# Turnout_Decoder_V1_2.net
KiCad netlist of a schematic drawn in EAGLE
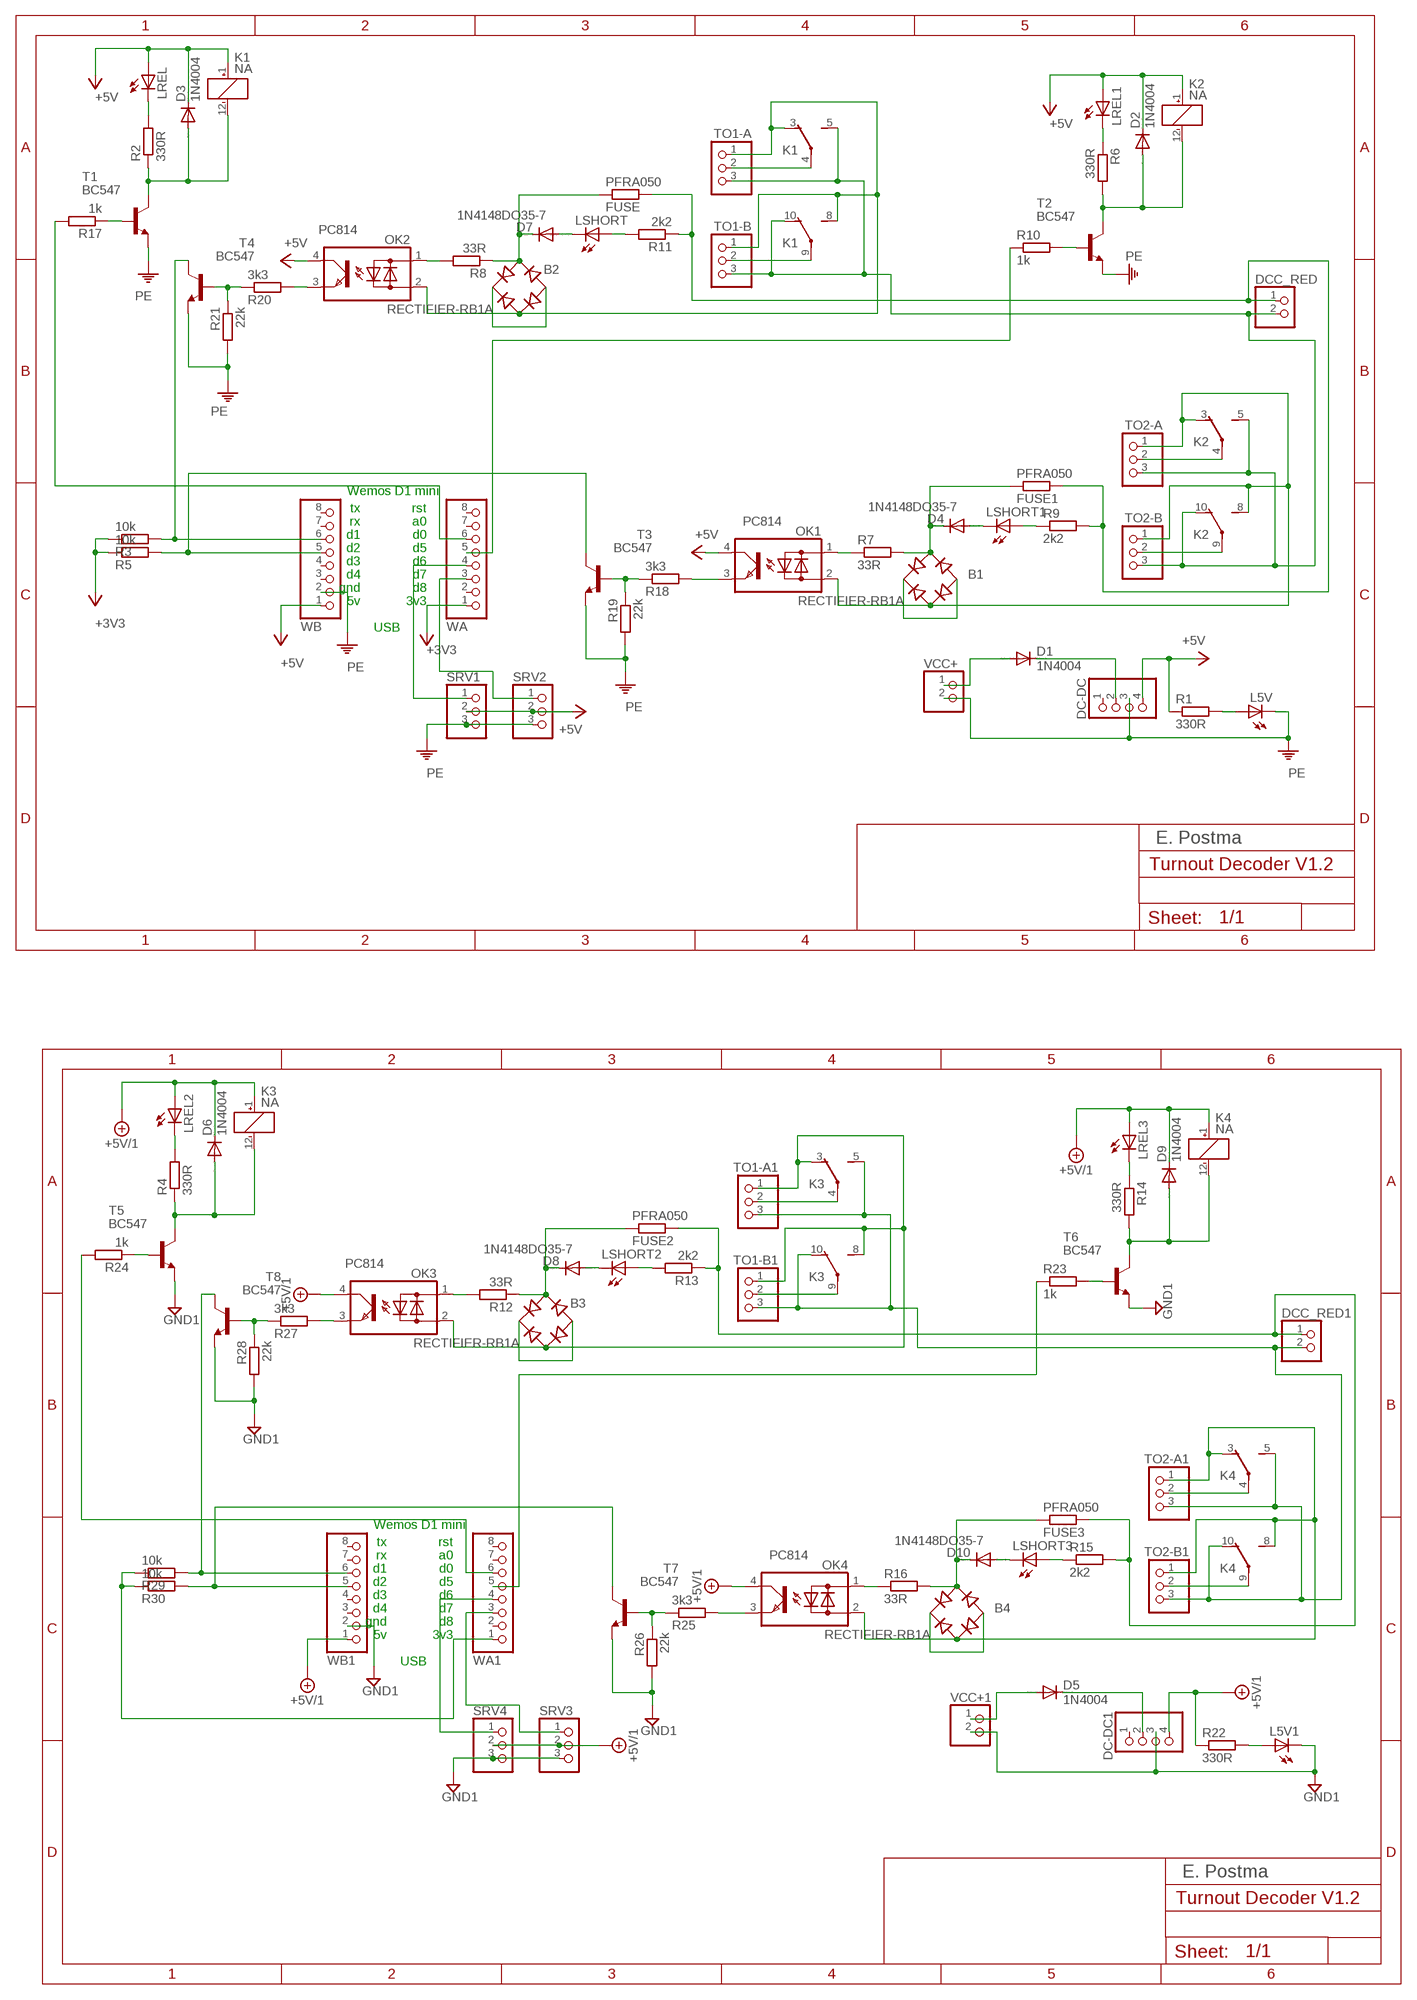
[diagram p0: schematic, sheet 1]

(export (version "E")
  (design (tool "Eeschema 10.0.6"))
  (components
    (comp (ref "B1")
      (value "RECTIFIER-RB1A")
      (footprint "eagle-import:RB1A")
      (libsource (lib "eagle-import") (part "RECTIFIER-RB1A"))
    )
    (comp (ref "B2")
      (value "RECTIFIER-RB1A")
      (footprint "eagle-import:RB1A")
      (libsource (lib "eagle-import") (part "RECTIFIER-RB1A"))
    )
    (comp (ref "B3")
      (value "RECTIFIER-RB1A")
      (footprint "eagle-import:RB1A")
      (libsource (lib "eagle-import") (part "RECTIFIER-RB1A"))
    )
    (comp (ref "B4")
      (value "RECTIFIER-RB1A")
      (footprint "eagle-import:RB1A")
      (libsource (lib "eagle-import") (part "RECTIFIER-RB1A"))
    )
    (comp (ref "D1")
      (value "1N4004")
      (footprint "eagle-import:DO41-10")
      (libsource (lib "eagle-import") (part "1N4004"))
    )
    (comp (ref "D2")
      (value "1N4004")
      (footprint "eagle-import:DO41-10")
      (libsource (lib "eagle-import") (part "1N4004"))
    )
    (comp (ref "D3")
      (value "1N4004")
      (footprint "eagle-import:DO41-10")
      (libsource (lib "eagle-import") (part "1N4004"))
    )
    (comp (ref "D4")
      (value "1N4148DO35-7")
      (footprint "eagle-import:DO35-7")
      (libsource (lib "eagle-import") (part "1N4148DO35-7"))
    )
    (comp (ref "D5")
      (value "1N4004")
      (footprint "eagle-import:DO41-10")
      (libsource (lib "eagle-import") (part "1N4004"))
    )
    (comp (ref "D6")
      (value "1N4004")
      (footprint "eagle-import:DO41-10")
      (libsource (lib "eagle-import") (part "1N4004"))
    )
    (comp (ref "D7")
      (value "1N4148DO35-7")
      (footprint "eagle-import:DO35-7")
      (libsource (lib "eagle-import") (part "1N4148DO35-7"))
    )
    (comp (ref "D8")
      (value "1N4148DO35-7")
      (footprint "eagle-import:DO35-7")
      (libsource (lib "eagle-import") (part "1N4148DO35-7"))
    )
    (comp (ref "D9")
      (value "1N4004")
      (footprint "eagle-import:DO41-10")
      (libsource (lib "eagle-import") (part "1N4004"))
    )
    (comp (ref "D10")
      (value "1N4148DO35-7")
      (footprint "eagle-import:DO35-7")
      (libsource (lib "eagle-import") (part "1N4148DO35-7"))
    )
    (comp (ref "DC-DC")
      (value "PINHD-1X4")
      (footprint "eagle-import:1X04")
      (libsource (lib "eagle-import") (part "PINHD-1X4"))
    )
    (comp (ref "DC-DC1")
      (value "PINHD-1X4")
      (footprint "eagle-import:1X04")
      (libsource (lib "eagle-import") (part "PINHD-1X4"))
    )
    (comp (ref "DCC_RED")
      (value "PINHD-1X2")
      (footprint "eagle-import:1X02")
      (libsource (lib "eagle-import") (part "PINHD-1X2"))
    )
    (comp (ref "DCC_RED1")
      (value "PINHD-1X2")
      (footprint "eagle-import:1X02")
      (libsource (lib "eagle-import") (part "PINHD-1X2"))
    )
    (comp (ref "FUSE")
      (value "PFRA050")
      (footprint "eagle-import:0414V")
      (libsource (lib "eagle-import") (part "R-EU_0414/5V"))
    )
    (comp (ref "FUSE1")
      (value "PFRA050")
      (footprint "eagle-import:0414V")
      (libsource (lib "eagle-import") (part "R-EU_0414/5V"))
    )
    (comp (ref "FUSE2")
      (value "PFRA050")
      (footprint "eagle-import:0414V")
      (libsource (lib "eagle-import") (part "R-EU_0414/5V"))
    )
    (comp (ref "FUSE3")
      (value "PFRA050")
      (footprint "eagle-import:0414V")
      (libsource (lib "eagle-import") (part "R-EU_0414/5V"))
    )
    (comp (ref "K1") (value "NA") (footprint "eagle-import:NA") (libsource (lib "eagle-import") (part "NA")))
    (comp (ref "K2") (value "NA") (footprint "eagle-import:NA") (libsource (lib "eagle-import") (part "NA")))
    (comp (ref "K3") (value "NA") (footprint "eagle-import:NA") (libsource (lib "eagle-import") (part "NA")))
    (comp (ref "K4") (value "NA") (footprint "eagle-import:NA") (libsource (lib "eagle-import") (part "NA")))
    (comp (ref "L5V")
      (value "LED3MM")
      (footprint "eagle-import:LED3MM")
      (libsource (lib "eagle-import") (part "LED3MM"))
    )
    (comp (ref "L5V1")
      (value "LED3MM")
      (footprint "eagle-import:LED3MM")
      (libsource (lib "eagle-import") (part "LED3MM"))
    )
    (comp (ref "LREL")
      (value "LED3MM")
      (footprint "eagle-import:LED3MM")
      (libsource (lib "eagle-import") (part "LED3MM"))
    )
    (comp (ref "LREL1")
      (value "LED3MM")
      (footprint "eagle-import:LED3MM")
      (libsource (lib "eagle-import") (part "LED3MM"))
    )
    (comp (ref "LREL2")
      (value "LED3MM")
      (footprint "eagle-import:LED3MM")
      (libsource (lib "eagle-import") (part "LED3MM"))
    )
    (comp (ref "LREL3")
      (value "LED3MM")
      (footprint "eagle-import:LED3MM")
      (libsource (lib "eagle-import") (part "LED3MM"))
    )
    (comp (ref "LSHORT")
      (value "LED3MM")
      (footprint "eagle-import:LED3MM")
      (libsource (lib "eagle-import") (part "LED3MM"))
    )
    (comp (ref "LSHORT1")
      (value "LED3MM")
      (footprint "eagle-import:LED3MM")
      (libsource (lib "eagle-import") (part "LED3MM"))
    )
    (comp (ref "LSHORT2")
      (value "LED3MM")
      (footprint "eagle-import:LED3MM")
      (libsource (lib "eagle-import") (part "LED3MM"))
    )
    (comp (ref "LSHORT3")
      (value "LED3MM")
      (footprint "eagle-import:LED3MM")
      (libsource (lib "eagle-import") (part "LED3MM"))
    )
    (comp (ref "OK1")
      (value "PC814")
      (footprint "eagle-import:DIL04")
      (libsource (lib "eagle-import") (part "PC814"))
    )
    (comp (ref "OK2")
      (value "PC814")
      (footprint "eagle-import:DIL04")
      (libsource (lib "eagle-import") (part "PC814"))
    )
    (comp (ref "OK3")
      (value "PC814")
      (footprint "eagle-import:DIL04")
      (libsource (lib "eagle-import") (part "PC814"))
    )
    (comp (ref "OK4")
      (value "PC814")
      (footprint "eagle-import:DIL04")
      (libsource (lib "eagle-import") (part "PC814"))
    )
    (comp (ref "R1")
      (value "330R")
      (footprint "eagle-import:0207_7")
      (libsource (lib "eagle-import") (part "resistor_348_R-EU_0207/7"))
    )
    (comp (ref "R2")
      (value "330R")
      (footprint "eagle-import:0207_7")
      (libsource (lib "eagle-import") (part "resistor_348_R-EU_0207/7"))
    )
    (comp (ref "R3")
      (value "10k")
      (footprint "eagle-import:0207_7")
      (libsource (lib "eagle-import") (part "resistor_348_R-EU_0207/7"))
    )
    (comp (ref "R4")
      (value "330R")
      (footprint "eagle-import:0207_7")
      (libsource (lib "eagle-import") (part "resistor_348_R-EU_0207/7"))
    )
    (comp (ref "R5")
      (value "10k")
      (footprint "eagle-import:0207_7")
      (libsource (lib "eagle-import") (part "resistor_348_R-EU_0207/7"))
    )
    (comp (ref "R6")
      (value "330R")
      (footprint "eagle-import:0207_7")
      (libsource (lib "eagle-import") (part "resistor_348_R-EU_0207/7"))
    )
    (comp (ref "R7")
      (value "33R")
      (footprint "eagle-import:0207_7")
      (libsource (lib "eagle-import") (part "resistor_348_R-EU_0207/7"))
    )
    (comp (ref "R8")
      (value "33R")
      (footprint "eagle-import:0207_7")
      (libsource (lib "eagle-import") (part "resistor_348_R-EU_0207/7"))
    )
    (comp (ref "R9")
      (value "2k2")
      (footprint "eagle-import:0207_7")
      (libsource (lib "eagle-import") (part "resistor_348_R-EU_0207/7"))
    )
    (comp (ref "R10")
      (value "1k")
      (footprint "eagle-import:0207_7")
      (libsource (lib "eagle-import") (part "resistor_348_R-EU_0207/7"))
    )
    (comp (ref "R11")
      (value "2k2")
      (footprint "eagle-import:0207_7")
      (libsource (lib "eagle-import") (part "resistor_348_R-EU_0207/7"))
    )
    (comp (ref "R12")
      (value "33R")
      (footprint "eagle-import:0207_7")
      (libsource (lib "eagle-import") (part "resistor_348_R-EU_0207/7"))
    )
    (comp (ref "R13")
      (value "2k2")
      (footprint "eagle-import:0207_7")
      (libsource (lib "eagle-import") (part "resistor_348_R-EU_0207/7"))
    )
    (comp (ref "R14")
      (value "330R")
      (footprint "eagle-import:0207_7")
      (libsource (lib "eagle-import") (part "resistor_348_R-EU_0207/7"))
    )
    (comp (ref "R15")
      (value "2k2")
      (footprint "eagle-import:0207_7")
      (libsource (lib "eagle-import") (part "resistor_348_R-EU_0207/7"))
    )
    (comp (ref "R16")
      (value "33R")
      (footprint "eagle-import:0207_7")
      (libsource (lib "eagle-import") (part "resistor_348_R-EU_0207/7"))
    )
    (comp (ref "R17")
      (value "1k")
      (footprint "eagle-import:0207_7")
      (libsource (lib "eagle-import") (part "resistor_348_R-EU_0207/7"))
    )
    (comp (ref "R18")
      (value "3k3")
      (footprint "eagle-import:0207_7")
      (libsource (lib "eagle-import") (part "resistor_348_R-EU_0207/7"))
    )
    (comp (ref "R19")
      (value "22k")
      (footprint "eagle-import:0207_7")
      (libsource (lib "eagle-import") (part "resistor_348_R-EU_0207/7"))
    )
    (comp (ref "R20")
      (value "3k3")
      (footprint "eagle-import:0207_7")
      (libsource (lib "eagle-import") (part "resistor_348_R-EU_0207/7"))
    )
    (comp (ref "R21")
      (value "22k")
      (footprint "eagle-import:0207_7")
      (libsource (lib "eagle-import") (part "resistor_348_R-EU_0207/7"))
    )
    (comp (ref "R22")
      (value "330R")
      (footprint "eagle-import:0207_7")
      (libsource (lib "eagle-import") (part "resistor_348_R-EU_0207/7"))
    )
    (comp (ref "R23")
      (value "1k")
      (footprint "eagle-import:0207_7")
      (libsource (lib "eagle-import") (part "resistor_348_R-EU_0207/7"))
    )
    (comp (ref "R24")
      (value "1k")
      (footprint "eagle-import:0207_7")
      (libsource (lib "eagle-import") (part "resistor_348_R-EU_0207/7"))
    )
    (comp (ref "R25")
      (value "3k3")
      (footprint "eagle-import:0207_7")
      (libsource (lib "eagle-import") (part "resistor_348_R-EU_0207/7"))
    )
    (comp (ref "R26")
      (value "22k")
      (footprint "eagle-import:0207_7")
      (libsource (lib "eagle-import") (part "resistor_348_R-EU_0207/7"))
    )
    (comp (ref "R27")
      (value "3k3")
      (footprint "eagle-import:0207_7")
      (libsource (lib "eagle-import") (part "resistor_348_R-EU_0207/7"))
    )
    (comp (ref "R28")
      (value "22k")
      (footprint "eagle-import:0207_7")
      (libsource (lib "eagle-import") (part "resistor_348_R-EU_0207/7"))
    )
    (comp (ref "R29")
      (value "10k")
      (footprint "eagle-import:0207_7")
      (libsource (lib "eagle-import") (part "resistor_348_R-EU_0207/7"))
    )
    (comp (ref "R30")
      (value "10k")
      (footprint "eagle-import:0207_7")
      (libsource (lib "eagle-import") (part "resistor_348_R-EU_0207/7"))
    )
    (comp (ref "SRV1")
      (value "PINHD-1X3")
      (footprint "eagle-import:1X03")
      (libsource (lib "eagle-import") (part "PINHD-1X3"))
    )
    (comp (ref "SRV2")
      (value "PINHD-1X3")
      (footprint "eagle-import:1X03")
      (libsource (lib "eagle-import") (part "PINHD-1X3"))
    )
    (comp (ref "SRV3")
      (value "PINHD-1X3")
      (footprint "eagle-import:1X03")
      (libsource (lib "eagle-import") (part "PINHD-1X3"))
    )
    (comp (ref "SRV4")
      (value "PINHD-1X3")
      (footprint "eagle-import:1X03")
      (libsource (lib "eagle-import") (part "PINHD-1X3"))
    )
    (comp (ref "T1")
      (value "BC547")
      (footprint "eagle-import:TO92")
      (libsource (lib "eagle-import") (part "BC547"))
    )
    (comp (ref "T2")
      (value "BC547")
      (footprint "eagle-import:TO92")
      (libsource (lib "eagle-import") (part "BC547"))
    )
    (comp (ref "T3")
      (value "BC547")
      (footprint "eagle-import:TO92")
      (libsource (lib "eagle-import") (part "BC547"))
    )
    (comp (ref "T4")
      (value "BC547")
      (footprint "eagle-import:TO92")
      (libsource (lib "eagle-import") (part "BC547"))
    )
    (comp (ref "T5")
      (value "BC547")
      (footprint "eagle-import:TO92")
      (libsource (lib "eagle-import") (part "BC547"))
    )
    (comp (ref "T6")
      (value "BC547")
      (footprint "eagle-import:TO92")
      (libsource (lib "eagle-import") (part "BC547"))
    )
    (comp (ref "T7")
      (value "BC547")
      (footprint "eagle-import:TO92")
      (libsource (lib "eagle-import") (part "BC547"))
    )
    (comp (ref "T8")
      (value "BC547")
      (footprint "eagle-import:TO92")
      (libsource (lib "eagle-import") (part "BC547"))
    )
    (comp (ref "TO1-A")
      (value "PINHD-1X3")
      (footprint "eagle-import:1X03")
      (libsource (lib "eagle-import") (part "PINHD-1X3"))
    )
    (comp (ref "TO1-A1")
      (value "PINHD-1X3")
      (footprint "eagle-import:1X03")
      (libsource (lib "eagle-import") (part "PINHD-1X3"))
    )
    (comp (ref "TO1-B")
      (value "PINHD-1X3")
      (footprint "eagle-import:1X03")
      (libsource (lib "eagle-import") (part "PINHD-1X3"))
    )
    (comp (ref "TO1-B1")
      (value "PINHD-1X3")
      (footprint "eagle-import:1X03")
      (libsource (lib "eagle-import") (part "PINHD-1X3"))
    )
    (comp (ref "TO2-A")
      (value "PINHD-1X3")
      (footprint "eagle-import:1X03")
      (libsource (lib "eagle-import") (part "PINHD-1X3"))
    )
    (comp (ref "TO2-A1")
      (value "PINHD-1X3")
      (footprint "eagle-import:1X03")
      (libsource (lib "eagle-import") (part "PINHD-1X3"))
    )
    (comp (ref "TO2-B")
      (value "PINHD-1X3")
      (footprint "eagle-import:1X03")
      (libsource (lib "eagle-import") (part "PINHD-1X3"))
    )
    (comp (ref "TO2-B1")
      (value "PINHD-1X3")
      (footprint "eagle-import:1X03")
      (libsource (lib "eagle-import") (part "PINHD-1X3"))
    )
    (comp (ref "VCC+")
      (value "PINHD-1X2")
      (footprint "eagle-import:1X02")
      (libsource (lib "eagle-import") (part "PINHD-1X2"))
    )
    (comp (ref "VCC+1")
      (value "PINHD-1X2")
      (footprint "eagle-import:1X02")
      (libsource (lib "eagle-import") (part "PINHD-1X2"))
    )
    (comp (ref "WA")
      (value "PINHD-1X8")
      (footprint "eagle-import:1X08")
      (libsource (lib "eagle-import") (part "PINHD-1X8"))
    )
    (comp (ref "WA1")
      (value "PINHD-1X8")
      (footprint "eagle-import:1X08")
      (libsource (lib "eagle-import") (part "PINHD-1X8"))
    )
    (comp (ref "WB")
      (value "PINHD-1X8")
      (footprint "eagle-import:1X08")
      (libsource (lib "eagle-import") (part "PINHD-1X8"))
    )
    (comp (ref "WB1")
      (value "PINHD-1X8")
      (footprint "eagle-import:1X08")
      (libsource (lib "eagle-import") (part "PINHD-1X8"))
    )
  )
  (nets
    (net (code "1") (name "+3V3") (class "Default")
      (node (ref "R3") (pin "1") (pinfunction "1_1") (pintype "passive"))
      (node (ref "R5") (pin "1") (pinfunction "1_1") (pintype "passive"))
      (node (ref "WA") (pin "1") (pinfunction "1_1") (pintype "passive"))
    )
    (net (code "2") (name "+5V") (class "Default")
      (node (ref "D2") (pin "C") (pinfunction "C_C") (pintype "passive"))
      (node (ref "D3") (pin "C") (pinfunction "C_C") (pintype "passive"))
      (node (ref "DC-DC") (pin "4") (pinfunction "4_4") (pintype "passive"))
      (node (ref "K1") (pin "1") (pinfunction "+_1") (pintype "passive"))
      (node (ref "K2") (pin "1") (pinfunction "+_1") (pintype "passive"))
      (node (ref "LREL") (pin "A") (pinfunction "A_A") (pintype "passive"))
      (node (ref "LREL1") (pin "A") (pinfunction "A_A") (pintype "passive"))
      (node (ref "OK1") (pin "4") (pinfunction "C_4") (pintype "passive"))
      (node (ref "OK2") (pin "4") (pinfunction "C_4") (pintype "passive"))
      (node (ref "R1") (pin "1") (pinfunction "1_1") (pintype "passive"))
      (node (ref "SRV1") (pin "2") (pinfunction "2_2") (pintype "passive"))
      (node (ref "SRV2") (pin "2") (pinfunction "2_2") (pintype "passive"))
      (node (ref "WB") (pin "1") (pinfunction "1_1") (pintype "passive"))
    )
    (net (code "3") (name "+5V{slash}1") (class "Default")
      (node (ref "D6") (pin "C") (pinfunction "C_C") (pintype "passive"))
      (node (ref "D9") (pin "C") (pinfunction "C_C") (pintype "passive"))
      (node (ref "DC-DC1") (pin "4") (pinfunction "4_4") (pintype "passive"))
      (node (ref "K3") (pin "1") (pinfunction "+_1") (pintype "passive"))
      (node (ref "K4") (pin "1") (pinfunction "+_1") (pintype "passive"))
      (node (ref "LREL2") (pin "A") (pinfunction "A_A") (pintype "passive"))
      (node (ref "LREL3") (pin "A") (pinfunction "A_A") (pintype "passive"))
      (node (ref "OK3") (pin "4") (pinfunction "C_4") (pintype "passive"))
      (node (ref "OK4") (pin "4") (pinfunction "C_4") (pintype "passive"))
      (node (ref "R22") (pin "1") (pinfunction "1_1") (pintype "passive"))
      (node (ref "SRV3") (pin "2") (pinfunction "2_2") (pintype "passive"))
      (node (ref "SRV4") (pin "2") (pinfunction "2_2") (pintype "passive"))
      (node (ref "WB1") (pin "1") (pinfunction "1_1") (pintype "passive"))
    )
    (net (code "4") (name "GND1") (class "Default")
      (node (ref "DC-DC1") (pin "3") (pinfunction "3_3") (pintype "passive"))
      (node (ref "L5V1") (pin "K") (pinfunction "C_K") (pintype "passive"))
      (node (ref "R26") (pin "2") (pinfunction "2_2") (pintype "passive"))
      (node (ref "R28") (pin "2") (pinfunction "2_2") (pintype "passive"))
      (node (ref "SRV3") (pin "3") (pinfunction "3_3") (pintype "passive"))
      (node (ref "SRV4") (pin "3") (pinfunction "3_3") (pintype "passive"))
      (node (ref "T5") (pin "1") (pinfunction "E_1") (pintype "passive"))
      (node (ref "T6") (pin "1") (pinfunction "E_1") (pintype "passive"))
      (node (ref "T7") (pin "1") (pinfunction "E_1") (pintype "passive"))
      (node (ref "T8") (pin "1") (pinfunction "E_1") (pintype "passive"))
      (node (ref "VCC+1") (pin "2") (pinfunction "2_2") (pintype "passive"))
      (node (ref "WB1") (pin "2") (pinfunction "2_2") (pintype "passive"))
    )
    (net (code "5") (name "Net-(B1-Pad+)") (class "Default")
      (node (ref "B1") (pin "+") (pinfunction "+_+") (pintype "passive"))
      (node (ref "B1") (pin "-") (pinfunction "-_-") (pintype "passive"))
    )
    (net (code "6") (name "Net-(B1-PadAC1)") (class "Default")
      (node (ref "B1") (pin "AC1") (pinfunction "AC1_AC1") (pintype "passive"))
      (node (ref "D4") (pin "C") (pinfunction "C_C") (pintype "passive"))
      (node (ref "FUSE1") (pin "1") (pinfunction "1_1") (pintype "passive"))
      (node (ref "R7") (pin "2") (pinfunction "2_2") (pintype "passive"))
    )
    (net (code "7") (name "Net-(B2-Pad+)") (class "Default")
      (node (ref "B2") (pin "+") (pinfunction "+_+") (pintype "passive"))
      (node (ref "B2") (pin "-") (pinfunction "-_-") (pintype "passive"))
    )
    (net (code "8") (name "Net-(B2-PadAC1)") (class "Default")
      (node (ref "B2") (pin "AC1") (pinfunction "AC1_AC1") (pintype "passive"))
      (node (ref "D7") (pin "C") (pinfunction "C_C") (pintype "passive"))
      (node (ref "FUSE") (pin "1") (pinfunction "1_1") (pintype "passive"))
      (node (ref "R8") (pin "1") (pinfunction "1_1") (pintype "passive"))
    )
    (net (code "9") (name "Net-(B3-Pad+)") (class "Default")
      (node (ref "B3") (pin "+") (pinfunction "+_+") (pintype "passive"))
      (node (ref "B3") (pin "-") (pinfunction "-_-") (pintype "passive"))
    )
    (net (code "10") (name "Net-(B3-PadAC1)") (class "Default")
      (node (ref "B3") (pin "AC1") (pinfunction "AC1_AC1") (pintype "passive"))
      (node (ref "D8") (pin "C") (pinfunction "C_C") (pintype "passive"))
      (node (ref "FUSE2") (pin "1") (pinfunction "1_1") (pintype "passive"))
      (node (ref "R12") (pin "1") (pinfunction "1_1") (pintype "passive"))
    )
    (net (code "11") (name "Net-(B4-Pad+)") (class "Default")
      (node (ref "B4") (pin "+") (pinfunction "+_+") (pintype "passive"))
      (node (ref "B4") (pin "-") (pinfunction "-_-") (pintype "passive"))
    )
    (net (code "12") (name "Net-(B4-PadAC1)") (class "Default")
      (node (ref "B4") (pin "AC1") (pinfunction "AC1_AC1") (pintype "passive"))
      (node (ref "D10") (pin "C") (pinfunction "C_C") (pintype "passive"))
      (node (ref "FUSE3") (pin "1") (pinfunction "1_1") (pintype "passive"))
      (node (ref "R16") (pin "2") (pinfunction "2_2") (pintype "passive"))
    )
    (net (code "13") (name "Net-(D1-PadA)") (class "Default")
      (node (ref "D1") (pin "A") (pinfunction "A_A") (pintype "passive"))
      (node (ref "VCC+") (pin "1") (pinfunction "1_1") (pintype "passive"))
    )
    (net (code "14") (name "Net-(D1-PadC)") (class "Default")
      (node (ref "D1") (pin "C") (pinfunction "C_C") (pintype "passive"))
      (node (ref "DC-DC") (pin "2") (pinfunction "2_2") (pintype "passive"))
    )
    (net (code "15") (name "Net-(D5-PadA)") (class "Default")
      (node (ref "D5") (pin "A") (pinfunction "A_A") (pintype "passive"))
      (node (ref "VCC+1") (pin "1") (pinfunction "1_1") (pintype "passive"))
    )
    (net (code "16") (name "Net-(D5-PadC)") (class "Default")
      (node (ref "D5") (pin "C") (pinfunction "C_C") (pintype "passive"))
      (node (ref "DC-DC1") (pin "2") (pinfunction "2_2") (pintype "passive"))
    )
    (net (code "17") (name "Net-(DCC_RED-Pad1)") (class "Default")
      (node (ref "DCC_RED") (pin "1") (pinfunction "1_1") (pintype "passive"))
      (node (ref "FUSE") (pin "2") (pinfunction "2_2") (pintype "passive"))
      (node (ref "FUSE1") (pin "2") (pinfunction "2_2") (pintype "passive"))
      (node (ref "R11") (pin "1") (pinfunction "1_1") (pintype "passive"))
      (node (ref "R9") (pin "2") (pinfunction "2_2") (pintype "passive"))
    )
    (net (code "18") (name "Net-(DCC_RED1-Pad1)") (class "Default")
      (node (ref "DCC_RED1") (pin "1") (pinfunction "1_1") (pintype "passive"))
      (node (ref "FUSE2") (pin "2") (pinfunction "2_2") (pintype "passive"))
      (node (ref "FUSE3") (pin "2") (pinfunction "2_2") (pintype "passive"))
      (node (ref "R13") (pin "1") (pinfunction "1_1") (pintype "passive"))
      (node (ref "R15") (pin "2") (pinfunction "2_2") (pintype "passive"))
    )
    (net (code "19") (name "Net-(K1A--)") (class "Default")
      (node (ref "D3") (pin "A") (pinfunction "A_A") (pintype "passive"))
      (node (ref "K1") (pin "12") (pinfunction "-_12") (pintype "passive"))
      (node (ref "R2") (pin "1") (pinfunction "1_1") (pintype "passive"))
      (node (ref "T1") (pin "3") (pinfunction "C_3") (pintype "passive"))
    )
    (net (code "20") (name "Net-(K1B-O)") (class "Default")
      (node (ref "B2") (pin "AC2") (pinfunction "AC2_AC2") (pintype "passive"))
      (node (ref "K1") (pin "3") (pinfunction "O_3") (pintype "passive"))
      (node (ref "K1") (pin "8") (pinfunction "S_8") (pintype "passive"))
      (node (ref "OK2") (pin "2") (pinfunction "AC2_2") (pintype "passive"))
      (node (ref "TO1-A") (pin "1") (pinfunction "1_1") (pintype "passive"))
      (node (ref "TO1-B") (pin "1") (pinfunction "1_1") (pintype "passive"))
    )
    (net (code "21") (name "Net-(K1B-P)") (class "Default")
      (node (ref "K1") (pin "4") (pinfunction "P_4") (pintype "passive"))
      (node (ref "TO1-A") (pin "2") (pinfunction "2_2") (pintype "passive"))
    )
    (net (code "22") (name "Net-(K1B-S)") (class "Default")
      (node (ref "DCC_RED") (pin "2") (pinfunction "2_2") (pintype "passive"))
      (node (ref "K1") (pin "10") (pinfunction "O_10") (pintype "passive"))
      (node (ref "K1") (pin "5") (pinfunction "S_5") (pintype "passive"))
      (node (ref "K2") (pin "10") (pinfunction "O_10") (pintype "passive"))
      (node (ref "K2") (pin "5") (pinfunction "S_5") (pintype "passive"))
      (node (ref "TO1-A") (pin "3") (pinfunction "3_3") (pintype "passive"))
      (node (ref "TO1-B") (pin "3") (pinfunction "3_3") (pintype "passive"))
      (node (ref "TO2-A") (pin "3") (pinfunction "3_3") (pintype "passive"))
      (node (ref "TO2-B") (pin "3") (pinfunction "3_3") (pintype "passive"))
    )
    (net (code "23") (name "Net-(K1C-P)") (class "Default")
      (node (ref "K1") (pin "9") (pinfunction "P_9") (pintype "passive"))
      (node (ref "TO1-B") (pin "2") (pinfunction "2_2") (pintype "passive"))
    )
    (net (code "24") (name "Net-(K2A--)") (class "Default")
      (node (ref "D2") (pin "A") (pinfunction "A_A") (pintype "passive"))
      (node (ref "K2") (pin "12") (pinfunction "-_12") (pintype "passive"))
      (node (ref "R6") (pin "2") (pinfunction "2_2") (pintype "passive"))
      (node (ref "T2") (pin "3") (pinfunction "C_3") (pintype "passive"))
    )
    (net (code "25") (name "Net-(K2B-O)") (class "Default")
      (node (ref "B1") (pin "AC2") (pinfunction "AC2_AC2") (pintype "passive"))
      (node (ref "K2") (pin "3") (pinfunction "O_3") (pintype "passive"))
      (node (ref "K2") (pin "8") (pinfunction "S_8") (pintype "passive"))
      (node (ref "OK1") (pin "2") (pinfunction "AC2_2") (pintype "passive"))
      (node (ref "TO2-A") (pin "1") (pinfunction "1_1") (pintype "passive"))
      (node (ref "TO2-B") (pin "1") (pinfunction "1_1") (pintype "passive"))
    )
    (net (code "26") (name "Net-(K2B-P)") (class "Default")
      (node (ref "K2") (pin "4") (pinfunction "P_4") (pintype "passive"))
      (node (ref "TO2-A") (pin "2") (pinfunction "2_2") (pintype "passive"))
    )
    (net (code "27") (name "Net-(K2C-P)") (class "Default")
      (node (ref "K2") (pin "9") (pinfunction "P_9") (pintype "passive"))
      (node (ref "TO2-B") (pin "2") (pinfunction "2_2") (pintype "passive"))
    )
    (net (code "28") (name "Net-(K3A--)") (class "Default")
      (node (ref "D6") (pin "A") (pinfunction "A_A") (pintype "passive"))
      (node (ref "K3") (pin "12") (pinfunction "-_12") (pintype "passive"))
      (node (ref "R4") (pin "1") (pinfunction "1_1") (pintype "passive"))
      (node (ref "T5") (pin "3") (pinfunction "C_3") (pintype "passive"))
    )
    (net (code "29") (name "Net-(K3B-O)") (class "Default")
      (node (ref "B3") (pin "AC2") (pinfunction "AC2_AC2") (pintype "passive"))
      (node (ref "K3") (pin "3") (pinfunction "O_3") (pintype "passive"))
      (node (ref "K3") (pin "8") (pinfunction "S_8") (pintype "passive"))
      (node (ref "OK3") (pin "2") (pinfunction "AC2_2") (pintype "passive"))
      (node (ref "TO1-A1") (pin "1") (pinfunction "1_1") (pintype "passive"))
      (node (ref "TO1-B1") (pin "1") (pinfunction "1_1") (pintype "passive"))
    )
    (net (code "30") (name "Net-(K3B-P)") (class "Default")
      (node (ref "K3") (pin "4") (pinfunction "P_4") (pintype "passive"))
      (node (ref "TO1-A1") (pin "2") (pinfunction "2_2") (pintype "passive"))
    )
    (net (code "31") (name "Net-(K3B-S)") (class "Default")
      (node (ref "DCC_RED1") (pin "2") (pinfunction "2_2") (pintype "passive"))
      (node (ref "K3") (pin "10") (pinfunction "O_10") (pintype "passive"))
      (node (ref "K3") (pin "5") (pinfunction "S_5") (pintype "passive"))
      (node (ref "K4") (pin "10") (pinfunction "O_10") (pintype "passive"))
      (node (ref "K4") (pin "5") (pinfunction "S_5") (pintype "passive"))
      (node (ref "TO1-A1") (pin "3") (pinfunction "3_3") (pintype "passive"))
      (node (ref "TO1-B1") (pin "3") (pinfunction "3_3") (pintype "passive"))
      (node (ref "TO2-A1") (pin "3") (pinfunction "3_3") (pintype "passive"))
      (node (ref "TO2-B1") (pin "3") (pinfunction "3_3") (pintype "passive"))
    )
    (net (code "32") (name "Net-(K3C-P)") (class "Default")
      (node (ref "K3") (pin "9") (pinfunction "P_9") (pintype "passive"))
      (node (ref "TO1-B1") (pin "2") (pinfunction "2_2") (pintype "passive"))
    )
    (net (code "33") (name "Net-(K4A--)") (class "Default")
      (node (ref "D9") (pin "A") (pinfunction "A_A") (pintype "passive"))
      (node (ref "K4") (pin "12") (pinfunction "-_12") (pintype "passive"))
      (node (ref "R14") (pin "2") (pinfunction "2_2") (pintype "passive"))
      (node (ref "T6") (pin "3") (pinfunction "C_3") (pintype "passive"))
    )
    (net (code "34") (name "Net-(K4B-O)") (class "Default")
      (node (ref "B4") (pin "AC2") (pinfunction "AC2_AC2") (pintype "passive"))
      (node (ref "K4") (pin "3") (pinfunction "O_3") (pintype "passive"))
      (node (ref "K4") (pin "8") (pinfunction "S_8") (pintype "passive"))
      (node (ref "OK4") (pin "2") (pinfunction "AC2_2") (pintype "passive"))
      (node (ref "TO2-A1") (pin "1") (pinfunction "1_1") (pintype "passive"))
      (node (ref "TO2-B1") (pin "1") (pinfunction "1_1") (pintype "passive"))
    )
    (net (code "35") (name "Net-(K4B-P)") (class "Default")
      (node (ref "K4") (pin "4") (pinfunction "P_4") (pintype "passive"))
      (node (ref "TO2-A1") (pin "2") (pinfunction "2_2") (pintype "passive"))
    )
    (net (code "36") (name "Net-(K4C-P)") (class "Default")
      (node (ref "K4") (pin "9") (pinfunction "P_9") (pintype "passive"))
      (node (ref "TO2-B1") (pin "2") (pinfunction "2_2") (pintype "passive"))
    )
    (net (code "37") (name "Net-(L5V-PadA)") (class "Default")
      (node (ref "L5V") (pin "A") (pinfunction "A_A") (pintype "passive"))
      (node (ref "R1") (pin "2") (pinfunction "2_2") (pintype "passive"))
    )
    (net (code "38") (name "Net-(L5V1-PadA)") (class "Default")
      (node (ref "L5V1") (pin "A") (pinfunction "A_A") (pintype "passive"))
      (node (ref "R22") (pin "2") (pinfunction "2_2") (pintype "passive"))
    )
    (net (code "39") (name "Net-(LREL-C)") (class "Default")
      (node (ref "LREL") (pin "K") (pinfunction "C_K") (pintype "passive"))
      (node (ref "R2") (pin "2") (pinfunction "2_2") (pintype "passive"))
    )
    (net (code "40") (name "Net-(LREL1-C)") (class "Default")
      (node (ref "LREL1") (pin "K") (pinfunction "C_K") (pintype "passive"))
      (node (ref "R6") (pin "1") (pinfunction "1_1") (pintype "passive"))
    )
    (net (code "41") (name "Net-(LREL2-C)") (class "Default")
      (node (ref "LREL2") (pin "K") (pinfunction "C_K") (pintype "passive"))
      (node (ref "R4") (pin "2") (pinfunction "2_2") (pintype "passive"))
    )
    (net (code "42") (name "Net-(LREL3-C)") (class "Default")
      (node (ref "LREL3") (pin "K") (pinfunction "C_K") (pintype "passive"))
      (node (ref "R14") (pin "1") (pinfunction "1_1") (pintype "passive"))
    )
    (net (code "43") (name "Net-(LSHORT-C)") (class "Default")
      (node (ref "D7") (pin "A") (pinfunction "A_A") (pintype "passive"))
      (node (ref "LSHORT") (pin "K") (pinfunction "C_K") (pintype "passive"))
    )
    (net (code "44") (name "Net-(LSHORT-PadA)") (class "Default")
      (node (ref "LSHORT") (pin "A") (pinfunction "A_A") (pintype "passive"))
      (node (ref "R11") (pin "2") (pinfunction "2_2") (pintype "passive"))
    )
    (net (code "45") (name "Net-(LSHORT1-C)") (class "Default")
      (node (ref "D4") (pin "A") (pinfunction "A_A") (pintype "passive"))
      (node (ref "LSHORT1") (pin "K") (pinfunction "C_K") (pintype "passive"))
    )
    (net (code "46") (name "Net-(LSHORT1-PadA)") (class "Default")
      (node (ref "LSHORT1") (pin "A") (pinfunction "A_A") (pintype "passive"))
      (node (ref "R9") (pin "1") (pinfunction "1_1") (pintype "passive"))
    )
    (net (code "47") (name "Net-(LSHORT2-C)") (class "Default")
      (node (ref "D8") (pin "A") (pinfunction "A_A") (pintype "passive"))
      (node (ref "LSHORT2") (pin "K") (pinfunction "C_K") (pintype "passive"))
    )
    (net (code "48") (name "Net-(LSHORT2-PadA)") (class "Default")
      (node (ref "LSHORT2") (pin "A") (pinfunction "A_A") (pintype "passive"))
      (node (ref "R13") (pin "2") (pinfunction "2_2") (pintype "passive"))
    )
    (net (code "49") (name "Net-(LSHORT3-C)") (class "Default")
      (node (ref "D10") (pin "A") (pinfunction "A_A") (pintype "passive"))
      (node (ref "LSHORT3") (pin "K") (pinfunction "C_K") (pintype "passive"))
    )
    (net (code "50") (name "Net-(LSHORT3-PadA)") (class "Default")
      (node (ref "LSHORT3") (pin "A") (pinfunction "A_A") (pintype "passive"))
      (node (ref "R15") (pin "1") (pinfunction "1_1") (pintype "passive"))
    )
    (net (code "51") (name "Net-(OK1-AC1)") (class "Default")
      (node (ref "OK1") (pin "1") (pinfunction "AC1_1") (pintype "passive"))
      (node (ref "R7") (pin "1") (pinfunction "1_1") (pintype "passive"))
    )
    (net (code "52") (name "Net-(OK1-E)") (class "Default")
      (node (ref "OK1") (pin "3") (pinfunction "E_3") (pintype "passive"))
      (node (ref "R18") (pin "2") (pinfunction "2_2") (pintype "passive"))
    )
    (net (code "53") (name "Net-(OK2-AC1)") (class "Default")
      (node (ref "OK2") (pin "1") (pinfunction "AC1_1") (pintype "passive"))
      (node (ref "R8") (pin "2") (pinfunction "2_2") (pintype "passive"))
    )
    (net (code "54") (name "Net-(OK2-E)") (class "Default")
      (node (ref "OK2") (pin "3") (pinfunction "E_3") (pintype "passive"))
      (node (ref "R20") (pin "2") (pinfunction "2_2") (pintype "passive"))
    )
    (net (code "55") (name "Net-(OK3-AC1)") (class "Default")
      (node (ref "OK3") (pin "1") (pinfunction "AC1_1") (pintype "passive"))
      (node (ref "R12") (pin "2") (pinfunction "2_2") (pintype "passive"))
    )
    (net (code "56") (name "Net-(OK3-E)") (class "Default")
      (node (ref "OK3") (pin "3") (pinfunction "E_3") (pintype "passive"))
      (node (ref "R27") (pin "2") (pinfunction "2_2") (pintype "passive"))
    )
    (net (code "57") (name "Net-(OK4-AC1)") (class "Default")
      (node (ref "OK4") (pin "1") (pinfunction "AC1_1") (pintype "passive"))
      (node (ref "R16") (pin "1") (pinfunction "1_1") (pintype "passive"))
    )
    (net (code "58") (name "Net-(OK4-E)") (class "Default")
      (node (ref "OK4") (pin "3") (pinfunction "E_3") (pintype "passive"))
      (node (ref "R25") (pin "2") (pinfunction "2_2") (pintype "passive"))
    )
    (net (code "59") (name "Net-(R10-Pad1)") (class "Default")
      (node (ref "R10") (pin "1") (pinfunction "1_1") (pintype "passive"))
      (node (ref "WA") (pin "5") (pinfunction "5_5") (pintype "passive"))
    )
    (net (code "60") (name "Net-(R17-Pad2)") (class "Default")
      (node (ref "R17") (pin "2") (pinfunction "2_2") (pintype "passive"))
      (node (ref "WA") (pin "6") (pinfunction "6_6") (pintype "passive"))
    )
    (net (code "61") (name "Net-(R23-Pad1)") (class "Default")
      (node (ref "R23") (pin "1") (pinfunction "1_1") (pintype "passive"))
      (node (ref "WA1") (pin "5") (pinfunction "5_5") (pintype "passive"))
    )
    (net (code "62") (name "Net-(R24-Pad2)") (class "Default")
      (node (ref "R24") (pin "2") (pinfunction "2_2") (pintype "passive"))
      (node (ref "WA1") (pin "6") (pinfunction "6_6") (pintype "passive"))
    )
    (net (code "63") (name "Net-(R29-Pad1)") (class "Default")
      (node (ref "R29") (pin "1") (pinfunction "1_1") (pintype "passive"))
      (node (ref "R30") (pin "1") (pinfunction "1_1") (pintype "passive"))
      (node (ref "WA1") (pin "1") (pinfunction "1_1") (pintype "passive"))
    )
    (net (code "64") (name "Net-(SRV1-Pad1)") (class "Default")
      (node (ref "SRV1") (pin "1") (pinfunction "1_1") (pintype "passive"))
      (node (ref "WA") (pin "4") (pinfunction "4_4") (pintype "passive"))
    )
    (net (code "65") (name "Net-(SRV2-Pad1)") (class "Default")
      (node (ref "SRV2") (pin "1") (pinfunction "1_1") (pintype "passive"))
      (node (ref "WA") (pin "3") (pinfunction "3_3") (pintype "passive"))
    )
    (net (code "66") (name "Net-(SRV3-Pad1)") (class "Default")
      (node (ref "SRV3") (pin "1") (pinfunction "1_1") (pintype "passive"))
      (node (ref "WA1") (pin "3") (pinfunction "3_3") (pintype "passive"))
    )
    (net (code "67") (name "Net-(SRV4-Pad1)") (class "Default")
      (node (ref "SRV4") (pin "1") (pinfunction "1_1") (pintype "passive"))
      (node (ref "WA1") (pin "4") (pinfunction "4_4") (pintype "passive"))
    )
    (net (code "68") (name "Net-(T1-B)") (class "Default")
      (node (ref "R17") (pin "1") (pinfunction "1_1") (pintype "passive"))
      (node (ref "T1") (pin "2") (pinfunction "B_2") (pintype "passive"))
    )
    (net (code "69") (name "Net-(T2-B)") (class "Default")
      (node (ref "R10") (pin "2") (pinfunction "2_2") (pintype "passive"))
      (node (ref "T2") (pin "2") (pinfunction "B_2") (pintype "passive"))
    )
    (net (code "70") (name "Net-(T3-B)") (class "Default")
      (node (ref "R18") (pin "1") (pinfunction "1_1") (pintype "passive"))
      (node (ref "R19") (pin "1") (pinfunction "1_1") (pintype "passive"))
      (node (ref "T3") (pin "2") (pinfunction "B_2") (pintype "passive"))
    )
    (net (code "71") (name "Net-(T3-C)") (class "Default")
      (node (ref "R5") (pin "2") (pinfunction "2_2") (pintype "passive"))
      (node (ref "T3") (pin "3") (pinfunction "C_3") (pintype "passive"))
      (node (ref "WB") (pin "5") (pinfunction "5_5") (pintype "passive"))
    )
    (net (code "72") (name "Net-(T4-B)") (class "Default")
      (node (ref "R20") (pin "1") (pinfunction "1_1") (pintype "passive"))
      (node (ref "R21") (pin "1") (pinfunction "1_1") (pintype "passive"))
      (node (ref "T4") (pin "2") (pinfunction "B_2") (pintype "passive"))
    )
    (net (code "73") (name "Net-(T4-C)") (class "Default")
      (node (ref "R3") (pin "2") (pinfunction "2_2") (pintype "passive"))
      (node (ref "T4") (pin "3") (pinfunction "C_3") (pintype "passive"))
      (node (ref "WB") (pin "6") (pinfunction "6_6") (pintype "passive"))
    )
    (net (code "74") (name "Net-(T5-B)") (class "Default")
      (node (ref "R24") (pin "1") (pinfunction "1_1") (pintype "passive"))
      (node (ref "T5") (pin "2") (pinfunction "B_2") (pintype "passive"))
    )
    (net (code "75") (name "Net-(T6-B)") (class "Default")
      (node (ref "R23") (pin "2") (pinfunction "2_2") (pintype "passive"))
      (node (ref "T6") (pin "2") (pinfunction "B_2") (pintype "passive"))
    )
    (net (code "76") (name "Net-(T7-B)") (class "Default")
      (node (ref "R25") (pin "1") (pinfunction "1_1") (pintype "passive"))
      (node (ref "R26") (pin "1") (pinfunction "1_1") (pintype "passive"))
      (node (ref "T7") (pin "2") (pinfunction "B_2") (pintype "passive"))
    )
    (net (code "77") (name "Net-(T7-C)") (class "Default")
      (node (ref "R30") (pin "2") (pinfunction "2_2") (pintype "passive"))
      (node (ref "T7") (pin "3") (pinfunction "C_3") (pintype "passive"))
      (node (ref "WB1") (pin "5") (pinfunction "5_5") (pintype "passive"))
    )
    (net (code "78") (name "Net-(T8-B)") (class "Default")
      (node (ref "R27") (pin "1") (pinfunction "1_1") (pintype "passive"))
      (node (ref "R28") (pin "1") (pinfunction "1_1") (pintype "passive"))
      (node (ref "T8") (pin "2") (pinfunction "B_2") (pintype "passive"))
    )
    (net (code "79") (name "Net-(T8-C)") (class "Default")
      (node (ref "R29") (pin "2") (pinfunction "2_2") (pintype "passive"))
      (node (ref "T8") (pin "3") (pinfunction "C_3") (pintype "passive"))
      (node (ref "WB1") (pin "6") (pinfunction "6_6") (pintype "passive"))
    )
    (net (code "80") (name "PE") (class "Default")
      (node (ref "DC-DC") (pin "3") (pinfunction "3_3") (pintype "passive"))
      (node (ref "L5V") (pin "K") (pinfunction "C_K") (pintype "passive"))
      (node (ref "R19") (pin "2") (pinfunction "2_2") (pintype "passive"))
      (node (ref "R21") (pin "2") (pinfunction "2_2") (pintype "passive"))
      (node (ref "SRV1") (pin "3") (pinfunction "3_3") (pintype "passive"))
      (node (ref "SRV2") (pin "3") (pinfunction "3_3") (pintype "passive"))
      (node (ref "T1") (pin "1") (pinfunction "E_1") (pintype "passive"))
      (node (ref "T2") (pin "1") (pinfunction "E_1") (pintype "passive"))
      (node (ref "T3") (pin "1") (pinfunction "E_1") (pintype "passive"))
      (node (ref "T4") (pin "1") (pinfunction "E_1") (pintype "passive"))
      (node (ref "VCC+") (pin "2") (pinfunction "2_2") (pintype "passive"))
      (node (ref "WB") (pin "2") (pinfunction "2_2") (pintype "passive"))
    )
    (net (code "81") (name "unconnected-(DC-DC-Pad1)") (class "Default")
      (node (ref "DC-DC") (pin "1") (pinfunction "1_1") (pintype "passive"))
    )
    (net (code "82") (name "unconnected-(DC-DC1-Pad1)") (class "Default")
      (node (ref "DC-DC1") (pin "1") (pinfunction "1_1") (pintype "passive"))
    )
    (net (code "83") (name "unconnected-(WA-Pad2)") (class "Default")
      (node (ref "WA") (pin "2") (pinfunction "2_2") (pintype "passive"))
    )
    (net (code "84") (name "unconnected-(WA-Pad7)") (class "Default")
      (node (ref "WA") (pin "7") (pinfunction "7_7") (pintype "passive"))
    )
    (net (code "85") (name "unconnected-(WA-Pad8)") (class "Default")
      (node (ref "WA") (pin "8") (pinfunction "8_8") (pintype "passive"))
    )
    (net (code "86") (name "unconnected-(WA1-Pad2)") (class "Default")
      (node (ref "WA1") (pin "2") (pinfunction "2_2") (pintype "passive"))
    )
    (net (code "87") (name "unconnected-(WA1-Pad7)") (class "Default")
      (node (ref "WA1") (pin "7") (pinfunction "7_7") (pintype "passive"))
    )
    (net (code "88") (name "unconnected-(WA1-Pad8)") (class "Default")
      (node (ref "WA1") (pin "8") (pinfunction "8_8") (pintype "passive"))
    )
    (net (code "89") (name "unconnected-(WB-Pad3)") (class "Default")
      (node (ref "WB") (pin "3") (pinfunction "3_3") (pintype "passive"))
    )
    (net (code "90") (name "unconnected-(WB-Pad4)") (class "Default")
      (node (ref "WB") (pin "4") (pinfunction "4_4") (pintype "passive"))
    )
    (net (code "91") (name "unconnected-(WB-Pad7)") (class "Default")
      (node (ref "WB") (pin "7") (pinfunction "7_7") (pintype "passive"))
    )
    (net (code "92") (name "unconnected-(WB-Pad8)") (class "Default")
      (node (ref "WB") (pin "8") (pinfunction "8_8") (pintype "passive"))
    )
    (net (code "93") (name "unconnected-(WB1-Pad3)") (class "Default")
      (node (ref "WB1") (pin "3") (pinfunction "3_3") (pintype "passive"))
    )
    (net (code "94") (name "unconnected-(WB1-Pad4)") (class "Default")
      (node (ref "WB1") (pin "4") (pinfunction "4_4") (pintype "passive"))
    )
    (net (code "95") (name "unconnected-(WB1-Pad7)") (class "Default")
      (node (ref "WB1") (pin "7") (pinfunction "7_7") (pintype "passive"))
    )
    (net (code "96") (name "unconnected-(WB1-Pad8)") (class "Default")
      (node (ref "WB1") (pin "8") (pinfunction "8_8") (pintype "passive"))
    )
  )
)
